# 1_AT-Link-EZ-V1_4.net
KiCad netlist of a schematic drawn in Altium Designer
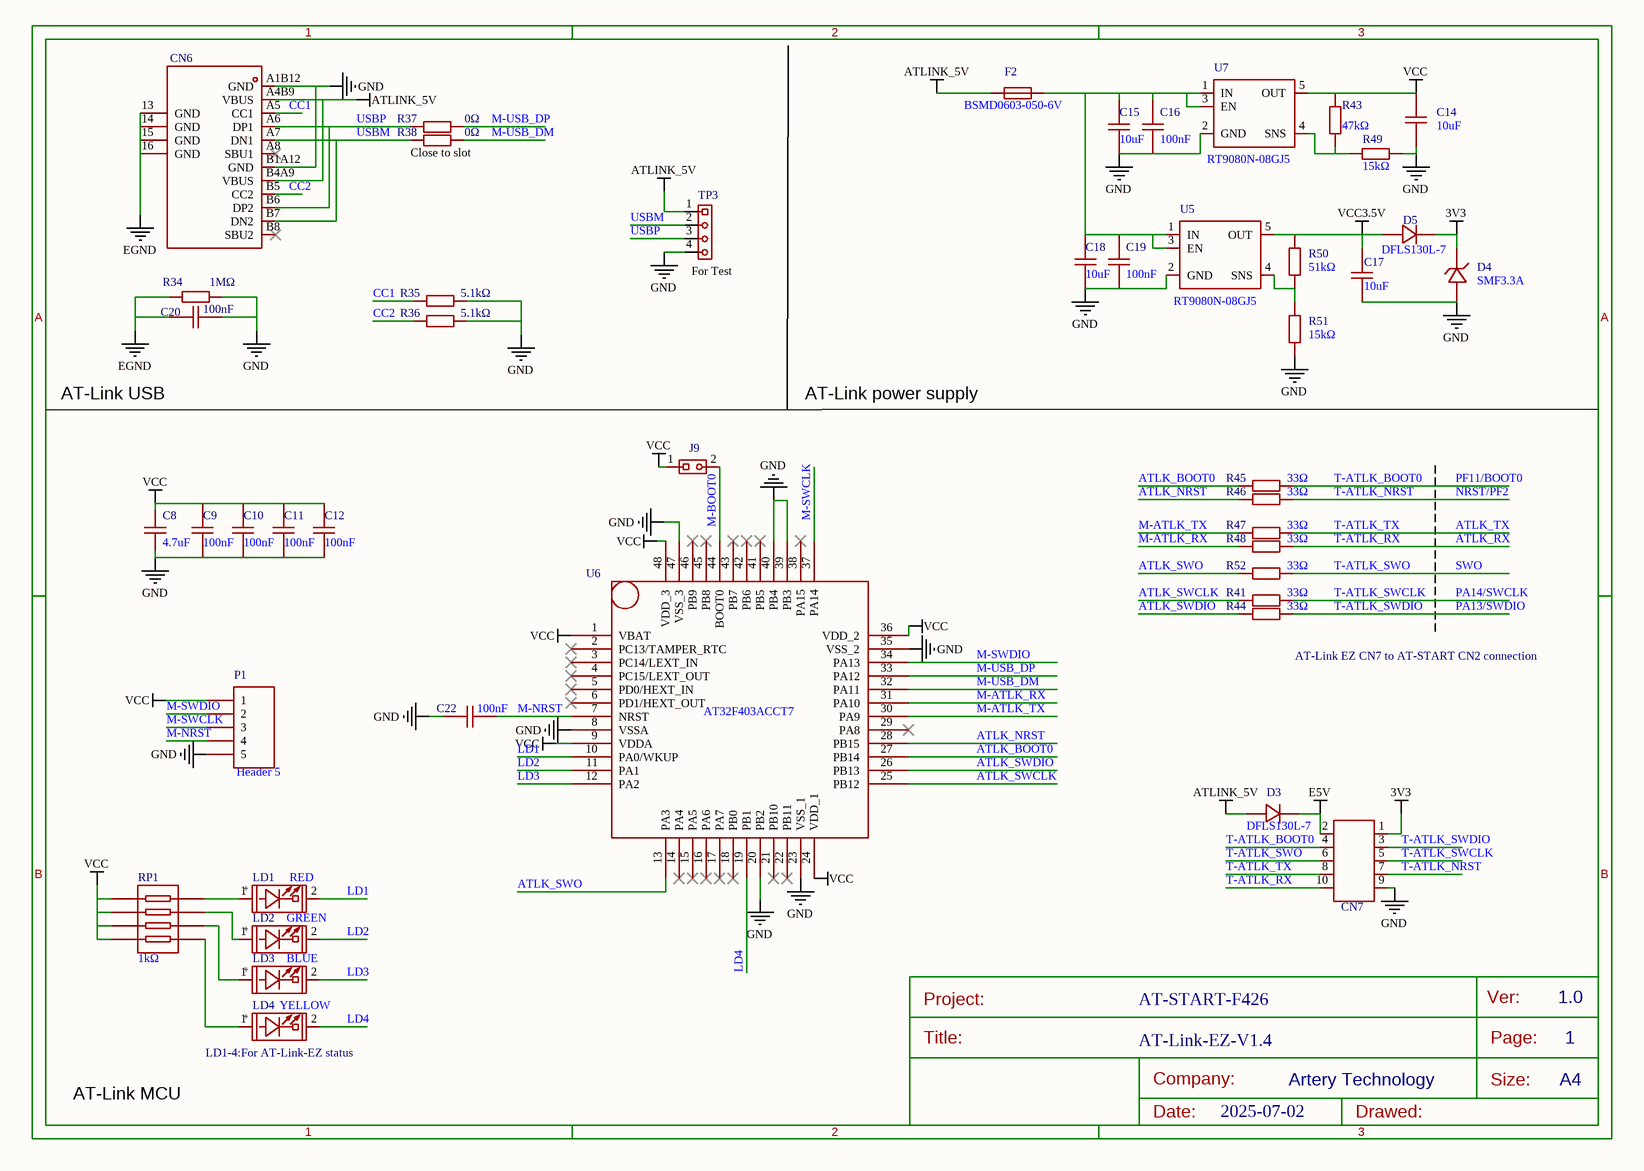
[diagram p0: 1_AT-Link-EZ-V1.4.schdoc]

(export (version "E")
  (design (tool "Eeschema 10.0.6"))
  (components
    (comp (ref "C8")
      (value "4.7uF")
      (footprint "C0603")
      (fields
        (field (name "MANUFACTURER PART") "CL10A475KO8NNNC")
        (field (name "MANUFACTURER") "SAMSUNG(三星)")
        (field (name "TOLERANCE") "±10%")
        (field (name "PUBLISHER") "Altium Limited")
      )
      (libsource (lib "altium-import") (part "root_1_CL10A475KO8NNNC_"))
    )
    (comp (ref "C9")
      (value "100nF")
      (footprint "C0603")
      (fields
        (field (name "MANUFACTURER") "YAGEO(国巨)")
        (field (name "MANUFACTURER PART") "CC0603KRX7R9BB104")
        (field (name "TOLERANCE") "±10%")
        (field (name "PUBLISHER") "Altium Limited")
      )
      (libsource (lib "altium-import") (part "root_1_CC0603KRX7R9BB104_"))
    )
    (comp (ref "C10")
      (value "100nF")
      (footprint "C0603")
      (fields
        (field (name "MANUFACTURER") "YAGEO(国巨)")
        (field (name "MANUFACTURER PART") "CC0603KRX7R9BB104")
        (field (name "TOLERANCE") "±10%")
        (field (name "PUBLISHER") "Altium Limited")
      )
      (libsource (lib "altium-import") (part "root_1_CC0603KRX7R9BB104_"))
    )
    (comp (ref "C11")
      (value "100nF")
      (footprint "C0603")
      (fields
        (field (name "MANUFACTURER") "YAGEO(国巨)")
        (field (name "MANUFACTURER PART") "CC0603KRX7R9BB104")
        (field (name "TOLERANCE") "±10%")
        (field (name "PUBLISHER") "Altium Limited")
      )
      (libsource (lib "altium-import") (part "root_1_CC0603KRX7R9BB104_"))
    )
    (comp (ref "C12")
      (value "100nF")
      (footprint "C0603")
      (fields
        (field (name "MANUFACTURER") "YAGEO(国巨)")
        (field (name "MANUFACTURER PART") "CC0603KRX7R9BB104")
        (field (name "TOLERANCE") "±10%")
        (field (name "PUBLISHER") "Altium Limited")
      )
      (libsource (lib "altium-import") (part "root_1_CC0603KRX7R9BB104_"))
    )
    (comp (ref "C14")
      (value "10uF")
      (footprint "C0603")
      (fields
        (field (name "MANUFACTURER") "SAMSUNG(三星)")
        (field (name "MANUFACTURER PART") "CL10A106KP8NNNC")
        (field (name "TOLERANCE") "±10%")
      )
      (libsource (lib "altium-import") (part "root_1_CL10A106KP8NNNC_"))
    )
    (comp (ref "C15")
      (value "10uF")
      (footprint "C0603")
      (fields
        (field (name "MANUFACTURER") "SAMSUNG(三星)")
        (field (name "MANUFACTURER PART") "CL10A106KP8NNNC")
        (field (name "TOLERANCE") "±10%")
      )
      (libsource (lib "altium-import") (part "root_1_CL10A106KP8NNNC_"))
    )
    (comp (ref "C16")
      (value "100nF")
      (footprint "C0603")
      (fields
        (field (name "MANUFACTURER") "YAGEO(国巨)")
        (field (name "MANUFACTURER PART") "CC0603KRX7R9BB104")
        (field (name "TOLERANCE") "±10%")
      )
      (libsource (lib "altium-import") (part "root_1_CC0603KRX7R9BB104_"))
    )
    (comp (ref "C17")
      (value "10uF")
      (footprint "C0603")
      (fields
        (field (name "MANUFACTURER") "SAMSUNG(三星)")
        (field (name "MANUFACTURER PART") "CL10A106KP8NNNC")
        (field (name "TOLERANCE") "±10%")
      )
      (libsource (lib "altium-import") (part "root_1_CL10A106KP8NNNC_"))
    )
    (comp (ref "C18")
      (value "10uF")
      (footprint "C0603")
      (fields
        (field (name "MANUFACTURER") "SAMSUNG(三星)")
        (field (name "MANUFACTURER PART") "CL10A106KP8NNNC")
        (field (name "TOLERANCE") "±10%")
      )
      (libsource (lib "altium-import") (part "root_1_CL10A106KP8NNNC_"))
    )
    (comp (ref "C19")
      (value "100nF")
      (footprint "C0603")
      (fields
        (field (name "MANUFACTURER") "YAGEO(国巨)")
        (field (name "MANUFACTURER PART") "CC0603KRX7R9BB104")
        (field (name "TOLERANCE") "±10%")
      )
      (libsource (lib "altium-import") (part "root_1_CC0603KRX7R9BB104_"))
    )
    (comp (ref "C20")
      (value "100nF")
      (footprint "C0603")
      (fields
        (field (name "MANUFACTURER") "YAGEO(国巨)")
        (field (name "MANUFACTURER PART") "CC0603KRX7R9BB104")
        (field (name "TOLERANCE") "±10%")
      )
      (libsource (lib "altium-import") (part "root_2_CC0603KRX7R9BB104_"))
    )
    (comp (ref "C22")
      (value "100nF")
      (footprint "C0603")
      (fields
        (field (name "MANUFACTURER") "YAGEO(国巨)")
        (field (name "MANUFACTURER PART") "CC0603KRX7R9BB104")
        (field (name "TOLERANCE") "±10%")
      )
      (libsource (lib "altium-import") (part "root_0_CC0603KRX7R9BB104_"))
    )
    (comp (ref "CN6")
      (value "~")
      (footprint "USB-C-SMD_TYPEC-304-BCP16")
      (fields (field (name "MANUFACTURER") "XUNPU(讯普)") (field (name "MANUFACTURER PART") "TYPEC-304-BCP16"))
      (libsource (lib "altium-import") (part "root_0_mirrored_TYPEC-304-BCP16_"))
    )
    (comp (ref "CN7")
      (value "CON10")
      (footprint "HDR2X5")
      (libsource (lib "altium-import") (part "root_0_mirrored_CON10_"))
    )
    (comp (ref "D3")
      (value "DFLS130L-7")
      (footprint "POWERDI-123_L2.8-W1.8-LS3.7-RD")
      (fields (field (name "MANUFACTURER") "DIODES(美台)") (field (name "PUBLISHER") "Altium Limited"))
      (libsource (lib "altium-import") (part "root_0_DFLS130L-7_"))
    )
    (comp (ref "D4")
      (value "SMF3.3A")
      (footprint "SOD-123FL_L2.8-W1.8-LS3.8-RD")
      (fields (field (name "MANUFACTURER") "Leiditech(雷卯电子)") (field (name "PUBLISHER") "Altium Limited"))
      (libsource (lib "altium-import") (part "root_3_SMF3.3A_C2759873_"))
    )
    (comp (ref "D5")
      (value "DFLS130L-7")
      (footprint "POWERDI-123_L2.8-W1.8-LS3.7-RD")
      (fields (field (name "MANUFACTURER") "DIODES(美台)") (field (name "PUBLISHER") "Altium Limited"))
      (libsource (lib "altium-import") (part "root_0_DFLS130L-7_"))
    )
    (comp (ref "F2")
      (value "BSMD0603-050-6V")
      (footprint "F0603")
      (fields (field (name "MANUFACTURER") "BHFUSE(佰宏)") (field (name "PUBLISHER") "Altium Limited"))
      (libsource (lib "altium-import") (part "root_0_BSMD0603-050-6V_"))
    )
    (comp (ref "J9")
      (value "1X2P_2.54M")
      (footprint "HDR1X2")
      (libsource (lib "altium-import") (part "root_0_1X2P_2.54M_"))
    )
    (comp (ref "LD1")
      (value "RED")
      (footprint "LED0603")
      (libsource (lib "altium-import") (part "root_0_RED_"))
    )
    (comp (ref "LD2")
      (value "GREEN")
      (footprint "LED0603")
      (libsource (lib "altium-import") (part "root_0_GREEN_"))
    )
    (comp (ref "LD3")
      (value "BLUE")
      (footprint "LED0603")
      (libsource (lib "altium-import") (part "root_0_BLUE_"))
    )
    (comp (ref "LD4")
      (value "YELLOW")
      (footprint "LED0603")
      (libsource (lib "altium-import") (part "root_0_YELLOW_"))
    )
    (comp (ref "P1")
      (value "Header 5")
      (footprint "HDR1X5")
      (fields (field (name "PUBLISHER") "Altium Limited"))
      (libsource (lib "altium-import") (part "root_0_Header 5_"))
    )
    (comp (ref "R34")
      (value "1MΩ")
      (footprint "R0603")
      (fields
        (field (name "MANUFACTURER") "YAGEO(国巨)")
        (field (name "MANUFACTURER PART") "RC0603FR-071ML")
        (field (name "TOLERANCE") "±1%")
      )
      (libsource (lib "altium-import") (part "root_0_RC0603FR-071ML_"))
    )
    (comp (ref "R35")
      (value "5.1kΩ")
      (footprint "R0603")
      (fields
        (field (name "MANUFACTURER") "UNI-ROYAL(厚声)")
        (field (name "MANUFACTURER PART") "0603WAF5101T5E")
        (field (name "TOLERANCE") "±1%")
      )
      (libsource (lib "altium-import") (part "root_0_0603WAF5101T5E_"))
    )
    (comp (ref "R36")
      (value "5.1kΩ")
      (footprint "R0603")
      (fields
        (field (name "MANUFACTURER") "UNI-ROYAL(厚声)")
        (field (name "MANUFACTURER PART") "0603WAF5101T5E")
        (field (name "TOLERANCE") "±1%")
      )
      (libsource (lib "altium-import") (part "root_0_0603WAF5101T5E_"))
    )
    (comp (ref "R37")
      (value "0Ω")
      (footprint "R0603")
      (fields
        (field (name "MANUFACTURER") "UNI-ROYAL(厚声)")
        (field (name "MANUFACTURER PART") "0603WAF0000T5E")
        (field (name "TOLERANCE") "±1%")
      )
      (libsource (lib "altium-import") (part "root_0_0603WAF0000T5E_"))
    )
    (comp (ref "R38")
      (value "0Ω")
      (footprint "R0603")
      (fields
        (field (name "MANUFACTURER") "UNI-ROYAL(厚声)")
        (field (name "MANUFACTURER PART") "0603WAF0000T5E")
        (field (name "TOLERANCE") "±1%")
      )
      (libsource (lib "altium-import") (part "root_0_0603WAF0000T5E_"))
    )
    (comp (ref "R41")
      (value "33Ω")
      (footprint "R0603")
      (fields
        (field (name "MANUFACTURER") "UNI-ROYAL(厚声)")
        (field (name "MANUFACTURER PART") "0603WAF330JT5E")
        (field (name "TOLERANCE") "±1%")
      )
      (libsource (lib "altium-import") (part "root_0_0603WAF330JT5E_"))
    )
    (comp (ref "R43")
      (value "47kΩ")
      (footprint "R0603")
      (fields
        (field (name "MANUFACTURER") "UNI-ROYAL(厚声)")
        (field (name "MANUFACTURER PART") "0603WAF4702T5E")
        (field (name "TOLERANCE") "±1%")
      )
      (libsource (lib "altium-import") (part "root_3_0603WAF4702T5E_"))
    )
    (comp (ref "R44")
      (value "33Ω")
      (footprint "R0603")
      (fields
        (field (name "MANUFACTURER") "UNI-ROYAL(厚声)")
        (field (name "MANUFACTURER PART") "0603WAF330JT5E")
        (field (name "TOLERANCE") "±1%")
      )
      (libsource (lib "altium-import") (part "root_0_0603WAF330JT5E_"))
    )
    (comp (ref "R45")
      (value "33Ω")
      (footprint "R0603")
      (fields
        (field (name "MANUFACTURER") "UNI-ROYAL(厚声)")
        (field (name "MANUFACTURER PART") "0603WAF330JT5E")
        (field (name "TOLERANCE") "±1%")
      )
      (libsource (lib "altium-import") (part "root_0_0603WAF330JT5E_"))
    )
    (comp (ref "R46")
      (value "33Ω")
      (footprint "R0603")
      (fields
        (field (name "MANUFACTURER") "UNI-ROYAL(厚声)")
        (field (name "MANUFACTURER PART") "0603WAF330JT5E")
        (field (name "TOLERANCE") "±1%")
      )
      (libsource (lib "altium-import") (part "root_0_0603WAF330JT5E_"))
    )
    (comp (ref "R47")
      (value "33Ω")
      (footprint "R0603")
      (fields
        (field (name "MANUFACTURER") "UNI-ROYAL(厚声)")
        (field (name "MANUFACTURER PART") "0603WAF330JT5E")
        (field (name "TOLERANCE") "±1%")
      )
      (libsource (lib "altium-import") (part "root_0_0603WAF330JT5E_"))
    )
    (comp (ref "R48")
      (value "33Ω")
      (footprint "R0603")
      (fields
        (field (name "MANUFACTURER") "UNI-ROYAL(厚声)")
        (field (name "MANUFACTURER PART") "0603WAF330JT5E")
        (field (name "TOLERANCE") "±1%")
      )
      (libsource (lib "altium-import") (part "root_0_0603WAF330JT5E_"))
    )
    (comp (ref "R49")
      (value "15kΩ")
      (footprint "R0603")
      (fields
        (field (name "MANUFACTURER") "UNI-ROYAL(厚声)")
        (field (name "MANUFACTURER PART") "0603WAF1502T5E")
        (field (name "TOLERANCE") "±1%")
      )
      (libsource (lib "altium-import") (part "root_0_0603WAF1502T5E_"))
    )
    (comp (ref "R50")
      (value "51kΩ")
      (footprint "R0603")
      (fields
        (field (name "MANUFACTURER") "UNI-ROYAL(厚声)")
        (field (name "MANUFACTURER PART") "0603WAF5102T5E")
        (field (name "TOLERANCE") "±1%")
      )
      (libsource (lib "altium-import") (part "root_3_0603WAF5102T5E_"))
    )
    (comp (ref "R51")
      (value "15kΩ")
      (footprint "R0603")
      (fields
        (field (name "MANUFACTURER") "UNI-ROYAL(厚声)")
        (field (name "MANUFACTURER PART") "0603WAF1502T5E")
        (field (name "TOLERANCE") "±1%")
      )
      (libsource (lib "altium-import") (part "root_3_0603WAF1502T5E_"))
    )
    (comp (ref "R52")
      (value "33Ω")
      (footprint "R0603")
      (fields
        (field (name "MANUFACTURER") "UNI-ROYAL(厚声)")
        (field (name "MANUFACTURER PART") "0603WAF330JT5E")
        (field (name "TOLERANCE") "±1%")
      )
      (libsource (lib "altium-import") (part "root_0_0603WAF330JT5E_"))
    )
    (comp (ref "RP1")
      (value "1kΩ")
      (footprint "RES-ARRAY-SMD_0603-8P-L3.2-W1.6-BL")
      (fields
        (field (name "MANUFACTURER") "UNI-ROYAL(厚声)")
        (field (name "MANUFACTURER PART") "4D03WGJ0102T5E")
        (field (name "TOLERANCE") "±5%")
      )
      (libsource (lib "altium-import") (part "root_0_4D03WGJ0102T5E_"))
    )
    (comp (ref "TP3")
      (value "1X4P_2.54F")
      (footprint "HDR1X4 - TOP")
      (libsource (lib "altium-import") (part "root_0_1X4P_2.54F_"))
    )
    (comp (ref "U5")
      (value "RT9080N-08GJ5")
      (footprint "SOT-23-5")
      (fields (field (name "LIBRARY NAME") "SCM_START_402F"))
      (libsource (lib "altium-import") (part "root_0_RT9080N-08GJ5_"))
    )
    (comp (ref "U6")
      (value "AT32F403ACCT7")
      (footprint "LQFP48 - 2")
      (libsource (lib "altium-import") (part "root_0_AT32F403CGT6_"))
    )
    (comp (ref "U7")
      (value "RT9080N-08GJ5")
      (footprint "SOT-23-5")
      (fields (field (name "LIBRARY NAME") "SCM_START_402F"))
      (libsource (lib "altium-import") (part "root_0_RT9080N-08GJ5_"))
    )
  )
  (nets
    (net (code "1") (name "/ATLK_BOOT0") (class "Default")
      (node (ref "R45") (pin "1") (pinfunction "1_1") (pintype "passive"))
      (node (ref "U6") (pin "27") (pinfunction "PB14_27") (pintype "passive"))
    )
    (net (code "2") (name "/ATLK_NRST") (class "Default")
      (node (ref "R46") (pin "1") (pinfunction "1_1") (pintype "passive"))
      (node (ref "U6") (pin "28") (pinfunction "PB15_28") (pintype "passive"))
    )
    (net (code "3") (name "/ATLK_RX") (class "Default")
      (node (ref "CN7") (pin "10") (pinfunction "10_10") (pintype "passive"))
      (node (ref "R48") (pin "2") (pinfunction "2_2") (pintype "passive"))
    )
    (net (code "4") (name "/ATLK_SWCLK") (class "Default")
      (node (ref "R41") (pin "1") (pinfunction "1_1") (pintype "passive"))
      (node (ref "U6") (pin "25") (pinfunction "PB12_25") (pintype "passive"))
    )
    (net (code "5") (name "/ATLK_SWDIO") (class "Default")
      (node (ref "R44") (pin "1") (pinfunction "1_1") (pintype "passive"))
      (node (ref "U6") (pin "26") (pinfunction "PB13_26") (pintype "passive"))
    )
    (net (code "6") (name "/ATLK_SWO") (class "Default")
      (node (ref "R52") (pin "1") (pinfunction "1_1") (pintype "passive"))
      (node (ref "U6") (pin "13") (pinfunction "PA3_13") (pintype "passive"))
    )
    (net (code "7") (name "/ATLK_TX") (class "Default")
      (node (ref "CN7") (pin "8") (pinfunction "8_8") (pintype "passive"))
      (node (ref "R47") (pin "2") (pinfunction "2_2") (pintype "passive"))
    )
    (net (code "8") (name "/CC1") (class "Default")
      (node (ref "CN6") (pin "A5") (pinfunction "CC1_A5") (pintype "passive"))
      (node (ref "R35") (pin "1") (pinfunction "1_1") (pintype "passive"))
    )
    (net (code "9") (name "/CC2") (class "Default")
      (node (ref "CN6") (pin "B5") (pinfunction "CC2_B5") (pintype "passive"))
      (node (ref "R36") (pin "1") (pinfunction "1_1") (pintype "passive"))
    )
    (net (code "10") (name "/LD1") (class "Default")
      (node (ref "LD1") (pin "2") (pinfunction "CATHODE_2") (pintype "passive"))
      (node (ref "U6") (pin "10") (pinfunction "PA0/WKUP_10") (pintype "passive"))
    )
    (net (code "11") (name "/LD2") (class "Default")
      (node (ref "LD2") (pin "2") (pinfunction "CATHODE_2") (pintype "passive"))
      (node (ref "U6") (pin "11") (pinfunction "PA1_11") (pintype "passive"))
    )
    (net (code "12") (name "/LD3") (class "Default")
      (node (ref "LD3") (pin "2") (pinfunction "CATHODE_2") (pintype "passive"))
      (node (ref "U6") (pin "12") (pinfunction "PA2_12") (pintype "passive"))
    )
    (net (code "13") (name "/LD4") (class "Default")
      (node (ref "LD4") (pin "2") (pinfunction "CATHODE_2") (pintype "passive"))
      (node (ref "U6") (pin "19") (pinfunction "PB1_19") (pintype "passive"))
    )
    (net (code "14") (name "/M-ATLK_RX") (class "Default")
      (node (ref "R48") (pin "1") (pinfunction "1_1") (pintype "passive"))
      (node (ref "U6") (pin "31") (pinfunction "PA10_31") (pintype "passive"))
    )
    (net (code "15") (name "/M-ATLK_TX") (class "Default")
      (node (ref "R47") (pin "1") (pinfunction "1_1") (pintype "passive"))
      (node (ref "U6") (pin "30") (pinfunction "PA9_30") (pintype "passive"))
    )
    (net (code "16") (name "/M-BOOT0") (class "Default")
      (node (ref "J9") (pin "2") (pinfunction "2_2") (pintype "passive"))
      (node (ref "U6") (pin "44") (pinfunction "BOOT0_44") (pintype "passive"))
    )
    (net (code "17") (name "/M-NRST") (class "Default")
      (node (ref "C22") (pin "2") (pinfunction "2_2") (pintype "passive"))
      (node (ref "P1") (pin "4") (pinfunction "4_4") (pintype "passive"))
      (node (ref "U6") (pin "7") (pinfunction "NRST_7") (pintype "passive"))
    )
    (net (code "18") (name "/M-SWCLK") (class "Default")
      (node (ref "P1") (pin "3") (pinfunction "3_3") (pintype "passive"))
      (node (ref "U6") (pin "37") (pinfunction "PA14_37") (pintype "passive"))
    )
    (net (code "19") (name "/M-SWDIO") (class "Default")
      (node (ref "P1") (pin "2") (pinfunction "2_2") (pintype "passive"))
      (node (ref "U6") (pin "34") (pinfunction "PA13_34") (pintype "passive"))
    )
    (net (code "20") (name "/M-USB_DM") (class "Default")
      (node (ref "R38") (pin "2") (pinfunction "2_2") (pintype "passive"))
      (node (ref "U6") (pin "32") (pinfunction "PA11_32") (pintype "passive"))
    )
    (net (code "21") (name "/M-USB_DP") (class "Default")
      (node (ref "R37") (pin "2") (pinfunction "2_2") (pintype "passive"))
      (node (ref "U6") (pin "33") (pinfunction "PA12_33") (pintype "passive"))
    )
    (net (code "22") (name "/NRST{slash}PF2") (class "Default")
      (node (ref "CN7") (pin "7") (pinfunction "7_7") (pintype "passive"))
      (node (ref "R46") (pin "2") (pinfunction "2_2") (pintype "passive"))
    )
    (net (code "23") (name "/PA13{slash}SWDIO") (class "Default")
      (node (ref "CN7") (pin "3") (pinfunction "3_3") (pintype "passive"))
      (node (ref "R44") (pin "2") (pinfunction "2_2") (pintype "passive"))
    )
    (net (code "24") (name "/PA14{slash}SWCLK") (class "Default")
      (node (ref "CN7") (pin "5") (pinfunction "5_5") (pintype "passive"))
      (node (ref "R41") (pin "2") (pinfunction "2_2") (pintype "passive"))
    )
    (net (code "25") (name "/PF11{slash}BOOT0") (class "Default")
      (node (ref "CN7") (pin "4") (pinfunction "4_4") (pintype "passive"))
      (node (ref "R45") (pin "2") (pinfunction "2_2") (pintype "passive"))
    )
    (net (code "26") (name "/SWO") (class "Default")
      (node (ref "CN7") (pin "6") (pinfunction "6_6") (pintype "passive"))
      (node (ref "R52") (pin "2") (pinfunction "2_2") (pintype "passive"))
    )
    (net (code "27") (name "/USBM") (class "Default")
      (node (ref "CN6") (pin "A7") (pinfunction "DN1_A7") (pintype "passive"))
      (node (ref "CN6") (pin "B7") (pinfunction "DN2_B7") (pintype "passive"))
      (node (ref "R38") (pin "1") (pinfunction "1_1") (pintype "passive"))
      (node (ref "TP3") (pin "2") (pinfunction "2_2") (pintype "passive"))
    )
    (net (code "28") (name "/USBP") (class "Default")
      (node (ref "CN6") (pin "A6") (pinfunction "DP1_A6") (pintype "passive"))
      (node (ref "CN6") (pin "B6") (pinfunction "DP2_B6") (pintype "passive"))
      (node (ref "R37") (pin "1") (pinfunction "1_1") (pintype "passive"))
      (node (ref "TP3") (pin "3") (pinfunction "3_3") (pintype "passive"))
    )
    (net (code "29") (name "3V3") (class "Default")
      (node (ref "CN7") (pin "1") (pinfunction "1_1") (pintype "passive"))
      (node (ref "D4") (pin "1") (pinfunction "C_1") (pintype "passive"))
      (node (ref "D5") (pin "1") (pinfunction "1_1") (pintype "passive"))
    )
    (net (code "30") (name "ATLINK_5V") (class "Default")
      (node (ref "CN6") (pin "A4B9") (pinfunction "VBUS_A4B9") (pintype "passive"))
      (node (ref "CN6") (pin "B4A9") (pinfunction "VBUS_B4A9") (pintype "passive"))
      (node (ref "D3") (pin "2") (pinfunction "2_2") (pintype "passive"))
      (node (ref "F2") (pin "1") (pinfunction "1_1") (pintype "passive"))
      (node (ref "TP3") (pin "1") (pinfunction "1_1") (pintype "passive"))
    )
    (net (code "31") (name "E5V") (class "Default")
      (node (ref "CN7") (pin "2") (pinfunction "2_2") (pintype "passive"))
      (node (ref "D3") (pin "1") (pinfunction "1_1") (pintype "passive"))
    )
    (net (code "32") (name "EGND") (class "Default")
      (node (ref "C20") (pin "2") (pinfunction "2_2") (pintype "passive"))
      (node (ref "CN6") (pin "13") (pinfunction "GND_13") (pintype "passive"))
      (node (ref "CN6") (pin "14") (pinfunction "GND_14") (pintype "passive"))
      (node (ref "CN6") (pin "15") (pinfunction "GND_15") (pintype "passive"))
      (node (ref "CN6") (pin "16") (pinfunction "GND_16") (pintype "passive"))
      (node (ref "R34") (pin "1") (pinfunction "1_1") (pintype "passive"))
    )
    (net (code "33") (name "GND") (class "Default")
      (node (ref "C10") (pin "1") (pinfunction "1_1") (pintype "passive"))
      (node (ref "C11") (pin "1") (pinfunction "1_1") (pintype "passive"))
      (node (ref "C12") (pin "1") (pinfunction "1_1") (pintype "passive"))
      (node (ref "C14") (pin "1") (pinfunction "1_1") (pintype "passive"))
      (node (ref "C15") (pin "1") (pinfunction "1_1") (pintype "passive"))
      (node (ref "C16") (pin "1") (pinfunction "1_1") (pintype "passive"))
      (node (ref "C17") (pin "1") (pinfunction "1_1") (pintype "passive"))
      (node (ref "C18") (pin "1") (pinfunction "1_1") (pintype "passive"))
      (node (ref "C19") (pin "1") (pinfunction "1_1") (pintype "passive"))
      (node (ref "C20") (pin "1") (pinfunction "1_1") (pintype "passive"))
      (node (ref "C22") (pin "1") (pinfunction "1_1") (pintype "passive"))
      (node (ref "C8") (pin "1") (pinfunction "1_1") (pintype "passive"))
      (node (ref "C9") (pin "1") (pinfunction "1_1") (pintype "passive"))
      (node (ref "CN6") (pin "A1B12") (pinfunction "GND_A1B12") (pintype "passive"))
      (node (ref "CN6") (pin "B1A12") (pinfunction "GND_B1A12") (pintype "passive"))
      (node (ref "CN7") (pin "9") (pinfunction "9_9") (pintype "passive"))
      (node (ref "D4") (pin "2") (pinfunction "A_2") (pintype "passive"))
      (node (ref "P1") (pin "5") (pinfunction "5_5") (pintype "passive"))
      (node (ref "R34") (pin "2") (pinfunction "2_2") (pintype "passive"))
      (node (ref "R35") (pin "2") (pinfunction "2_2") (pintype "passive"))
      (node (ref "R36") (pin "2") (pinfunction "2_2") (pintype "passive"))
      (node (ref "R49") (pin "2") (pinfunction "2_2") (pintype "passive"))
      (node (ref "R51") (pin "2") (pinfunction "2_2") (pintype "passive"))
      (node (ref "TP3") (pin "4") (pinfunction "4_4") (pintype "passive"))
      (node (ref "U5") (pin "2") (pinfunction "GND_2") (pintype "passive"))
      (node (ref "U6") (pin "20") (pinfunction "PB2_20") (pintype "passive"))
      (node (ref "U6") (pin "23") (pinfunction "VSS_1_23") (pintype "passive"))
      (node (ref "U6") (pin "35") (pinfunction "VSS_2_35") (pintype "passive"))
      (node (ref "U6") (pin "39") (pinfunction "PB3_39") (pintype "passive"))
      (node (ref "U6") (pin "40") (pinfunction "PB4_40") (pintype "passive"))
      (node (ref "U6") (pin "47") (pinfunction "VSS_3_47") (pintype "passive"))
      (node (ref "U6") (pin "8") (pinfunction "VSSA_8") (pintype "passive"))
      (node (ref "U7") (pin "2") (pinfunction "GND_2") (pintype "passive"))
    )
    (net (code "34") (name "Net-(LD1-ANODE)") (class "Default")
      (node (ref "LD1") (pin "1") (pinfunction "ANODE_1") (pintype "passive"))
      (node (ref "RP1") (pin "8") (pinfunction "8_8") (pintype "passive"))
    )
    (net (code "35") (name "Net-(LD2-ANODE)") (class "Default")
      (node (ref "LD2") (pin "1") (pinfunction "ANODE_1") (pintype "passive"))
      (node (ref "RP1") (pin "7") (pinfunction "7_7") (pintype "passive"))
    )
    (net (code "36") (name "Net-(LD3-ANODE)") (class "Default")
      (node (ref "LD3") (pin "1") (pinfunction "ANODE_1") (pintype "passive"))
      (node (ref "RP1") (pin "6") (pinfunction "6_6") (pintype "passive"))
    )
    (net (code "37") (name "Net-(LD4-ANODE)") (class "Default")
      (node (ref "LD4") (pin "1") (pinfunction "ANODE_1") (pintype "passive"))
      (node (ref "RP1") (pin "5") (pinfunction "5_5") (pintype "passive"))
    )
    (net (code "38") (name "Net-(U5-EN)") (class "Default")
      (node (ref "C15") (pin "2") (pinfunction "2_2") (pintype "passive"))
      (node (ref "C16") (pin "2") (pinfunction "2_2") (pintype "passive"))
      (node (ref "C18") (pin "2") (pinfunction "2_2") (pintype "passive"))
      (node (ref "C19") (pin "2") (pinfunction "2_2") (pintype "passive"))
      (node (ref "F2") (pin "2") (pinfunction "2_2") (pintype "passive"))
      (node (ref "U5") (pin "1") (pinfunction "IN_1") (pintype "passive"))
      (node (ref "U5") (pin "3") (pinfunction "EN_3") (pintype "passive"))
      (node (ref "U7") (pin "1") (pinfunction "IN_1") (pintype "passive"))
      (node (ref "U7") (pin "3") (pinfunction "EN_3") (pintype "passive"))
    )
    (net (code "39") (name "Net-(U5-SNS)") (class "Default")
      (node (ref "R50") (pin "2") (pinfunction "2_2") (pintype "passive"))
      (node (ref "R51") (pin "1") (pinfunction "1_1") (pintype "passive"))
      (node (ref "U5") (pin "4") (pinfunction "SNS_4") (pintype "passive"))
    )
    (net (code "40") (name "Net-(U7-SNS)") (class "Default")
      (node (ref "R43") (pin "2") (pinfunction "2_2") (pintype "passive"))
      (node (ref "R49") (pin "1") (pinfunction "1_1") (pintype "passive"))
      (node (ref "U7") (pin "4") (pinfunction "SNS_4") (pintype "passive"))
    )
    (net (code "41") (name "VCC") (class "Default")
      (node (ref "C10") (pin "2") (pinfunction "2_2") (pintype "passive"))
      (node (ref "C11") (pin "2") (pinfunction "2_2") (pintype "passive"))
      (node (ref "C12") (pin "2") (pinfunction "2_2") (pintype "passive"))
      (node (ref "C14") (pin "2") (pinfunction "2_2") (pintype "passive"))
      (node (ref "C8") (pin "2") (pinfunction "2_2") (pintype "passive"))
      (node (ref "C9") (pin "2") (pinfunction "2_2") (pintype "passive"))
      (node (ref "J9") (pin "1") (pinfunction "1_1") (pintype "passive"))
      (node (ref "P1") (pin "1") (pinfunction "1_1") (pintype "passive"))
      (node (ref "R43") (pin "1") (pinfunction "1_1") (pintype "passive"))
      (node (ref "RP1") (pin "1") (pinfunction "1_1") (pintype "passive"))
      (node (ref "RP1") (pin "2") (pinfunction "2_2") (pintype "passive"))
      (node (ref "RP1") (pin "3") (pinfunction "3_3") (pintype "passive"))
      (node (ref "RP1") (pin "4") (pinfunction "4_4") (pintype "passive"))
      (node (ref "U6") (pin "1") (pinfunction "VBAT_1") (pintype "passive"))
      (node (ref "U6") (pin "24") (pinfunction "VDD_1_24") (pintype "passive"))
      (node (ref "U6") (pin "36") (pinfunction "VDD_2_36") (pintype "passive"))
      (node (ref "U6") (pin "48") (pinfunction "VDD_3_48") (pintype "passive"))
      (node (ref "U6") (pin "9") (pinfunction "VDDA_9") (pintype "passive"))
      (node (ref "U7") (pin "5") (pinfunction "OUT_5") (pintype "passive"))
    )
    (net (code "42") (name "VCC3.5V") (class "Default")
      (node (ref "C17") (pin "2") (pinfunction "2_2") (pintype "passive"))
      (node (ref "D5") (pin "2") (pinfunction "2_2") (pintype "passive"))
      (node (ref "R50") (pin "1") (pinfunction "1_1") (pintype "passive"))
      (node (ref "U5") (pin "5") (pinfunction "OUT_5") (pintype "passive"))
    )
    (net (code "43") (name "unconnected-(CN6-SBU1-PadA8)") (class "Default")
      (node (ref "CN6") (pin "A8") (pinfunction "SBU1_A8") (pintype "passive+no_connect"))
    )
    (net (code "44") (name "unconnected-(CN6-SBU2-PadB8)") (class "Default")
      (node (ref "CN6") (pin "B8") (pinfunction "SBU2_B8") (pintype "passive+no_connect"))
    )
    (net (code "45") (name "unconnected-(U6-PA4-Pad14)") (class "Default")
      (node (ref "U6") (pin "14") (pinfunction "PA4_14") (pintype "passive+no_connect"))
    )
    (net (code "46") (name "unconnected-(U6-PA5-Pad15)") (class "Default")
      (node (ref "U6") (pin "15") (pinfunction "PA5_15") (pintype "passive+no_connect"))
    )
    (net (code "47") (name "unconnected-(U6-PA6-Pad16)") (class "Default")
      (node (ref "U6") (pin "16") (pinfunction "PA6_16") (pintype "passive+no_connect"))
    )
    (net (code "48") (name "unconnected-(U6-PA7-Pad17)") (class "Default")
      (node (ref "U6") (pin "17") (pinfunction "PA7_17") (pintype "passive+no_connect"))
    )
    (net (code "49") (name "unconnected-(U6-PA8-Pad29)") (class "Default")
      (node (ref "U6") (pin "29") (pinfunction "PA8_29") (pintype "passive+no_connect"))
    )
    (net (code "50") (name "unconnected-(U6-PA15-Pad38)") (class "Default")
      (node (ref "U6") (pin "38") (pinfunction "PA15_38") (pintype "passive+no_connect"))
    )
    (net (code "51") (name "unconnected-(U6-PB0-Pad18)") (class "Default")
      (node (ref "U6") (pin "18") (pinfunction "PB0_18") (pintype "passive+no_connect"))
    )
    (net (code "52") (name "unconnected-(U6-PB5-Pad41)") (class "Default")
      (node (ref "U6") (pin "41") (pinfunction "PB5_41") (pintype "passive+no_connect"))
    )
    (net (code "53") (name "unconnected-(U6-PB6-Pad42)") (class "Default")
      (node (ref "U6") (pin "42") (pinfunction "PB6_42") (pintype "passive+no_connect"))
    )
    (net (code "54") (name "unconnected-(U6-PB7-Pad43)") (class "Default")
      (node (ref "U6") (pin "43") (pinfunction "PB7_43") (pintype "passive+no_connect"))
    )
    (net (code "55") (name "unconnected-(U6-PB8-Pad45)") (class "Default")
      (node (ref "U6") (pin "45") (pinfunction "PB8_45") (pintype "passive+no_connect"))
    )
    (net (code "56") (name "unconnected-(U6-PB9-Pad46)") (class "Default")
      (node (ref "U6") (pin "46") (pinfunction "PB9_46") (pintype "passive+no_connect"))
    )
    (net (code "57") (name "unconnected-(U6-PB10-Pad21)") (class "Default")
      (node (ref "U6") (pin "21") (pinfunction "PB10_21") (pintype "passive+no_connect"))
    )
    (net (code "58") (name "unconnected-(U6-PB11-Pad22)") (class "Default")
      (node (ref "U6") (pin "22") (pinfunction "PB11_22") (pintype "passive+no_connect"))
    )
    (net (code "59") (name "unconnected-(U6-PC13{slash}TAMPER_RTC-Pad2)") (class "Default")
      (node (ref "U6") (pin "2") (pinfunction "PC13/TAMPER_RTC_2") (pintype "passive+no_connect"))
    )
    (net (code "60") (name "unconnected-(U6-PC14{slash}LEXT_IN-Pad3)") (class "Default")
      (node (ref "U6") (pin "3") (pinfunction "PC14/LEXT_IN_3") (pintype "passive+no_connect"))
    )
    (net (code "61") (name "unconnected-(U6-PC15{slash}LEXT_OUT-Pad4)") (class "Default")
      (node (ref "U6") (pin "4") (pinfunction "PC15/LEXT_OUT_4") (pintype "passive+no_connect"))
    )
    (net (code "62") (name "unconnected-(U6-PD0{slash}HEXT_IN-Pad5)") (class "Default")
      (node (ref "U6") (pin "5") (pinfunction "PD0/HEXT_IN_5") (pintype "passive+no_connect"))
    )
    (net (code "63") (name "unconnected-(U6-PD1{slash}HEXT_OUT-Pad6)") (class "Default")
      (node (ref "U6") (pin "6") (pinfunction "PD1/HEXT_OUT_6") (pintype "passive+no_connect"))
    )
  )
)
